# 24Vto12V_v2_1_2025-04-05_21-50-08.net
KiCad netlist of a schematic drawn in EasyEDA Pro
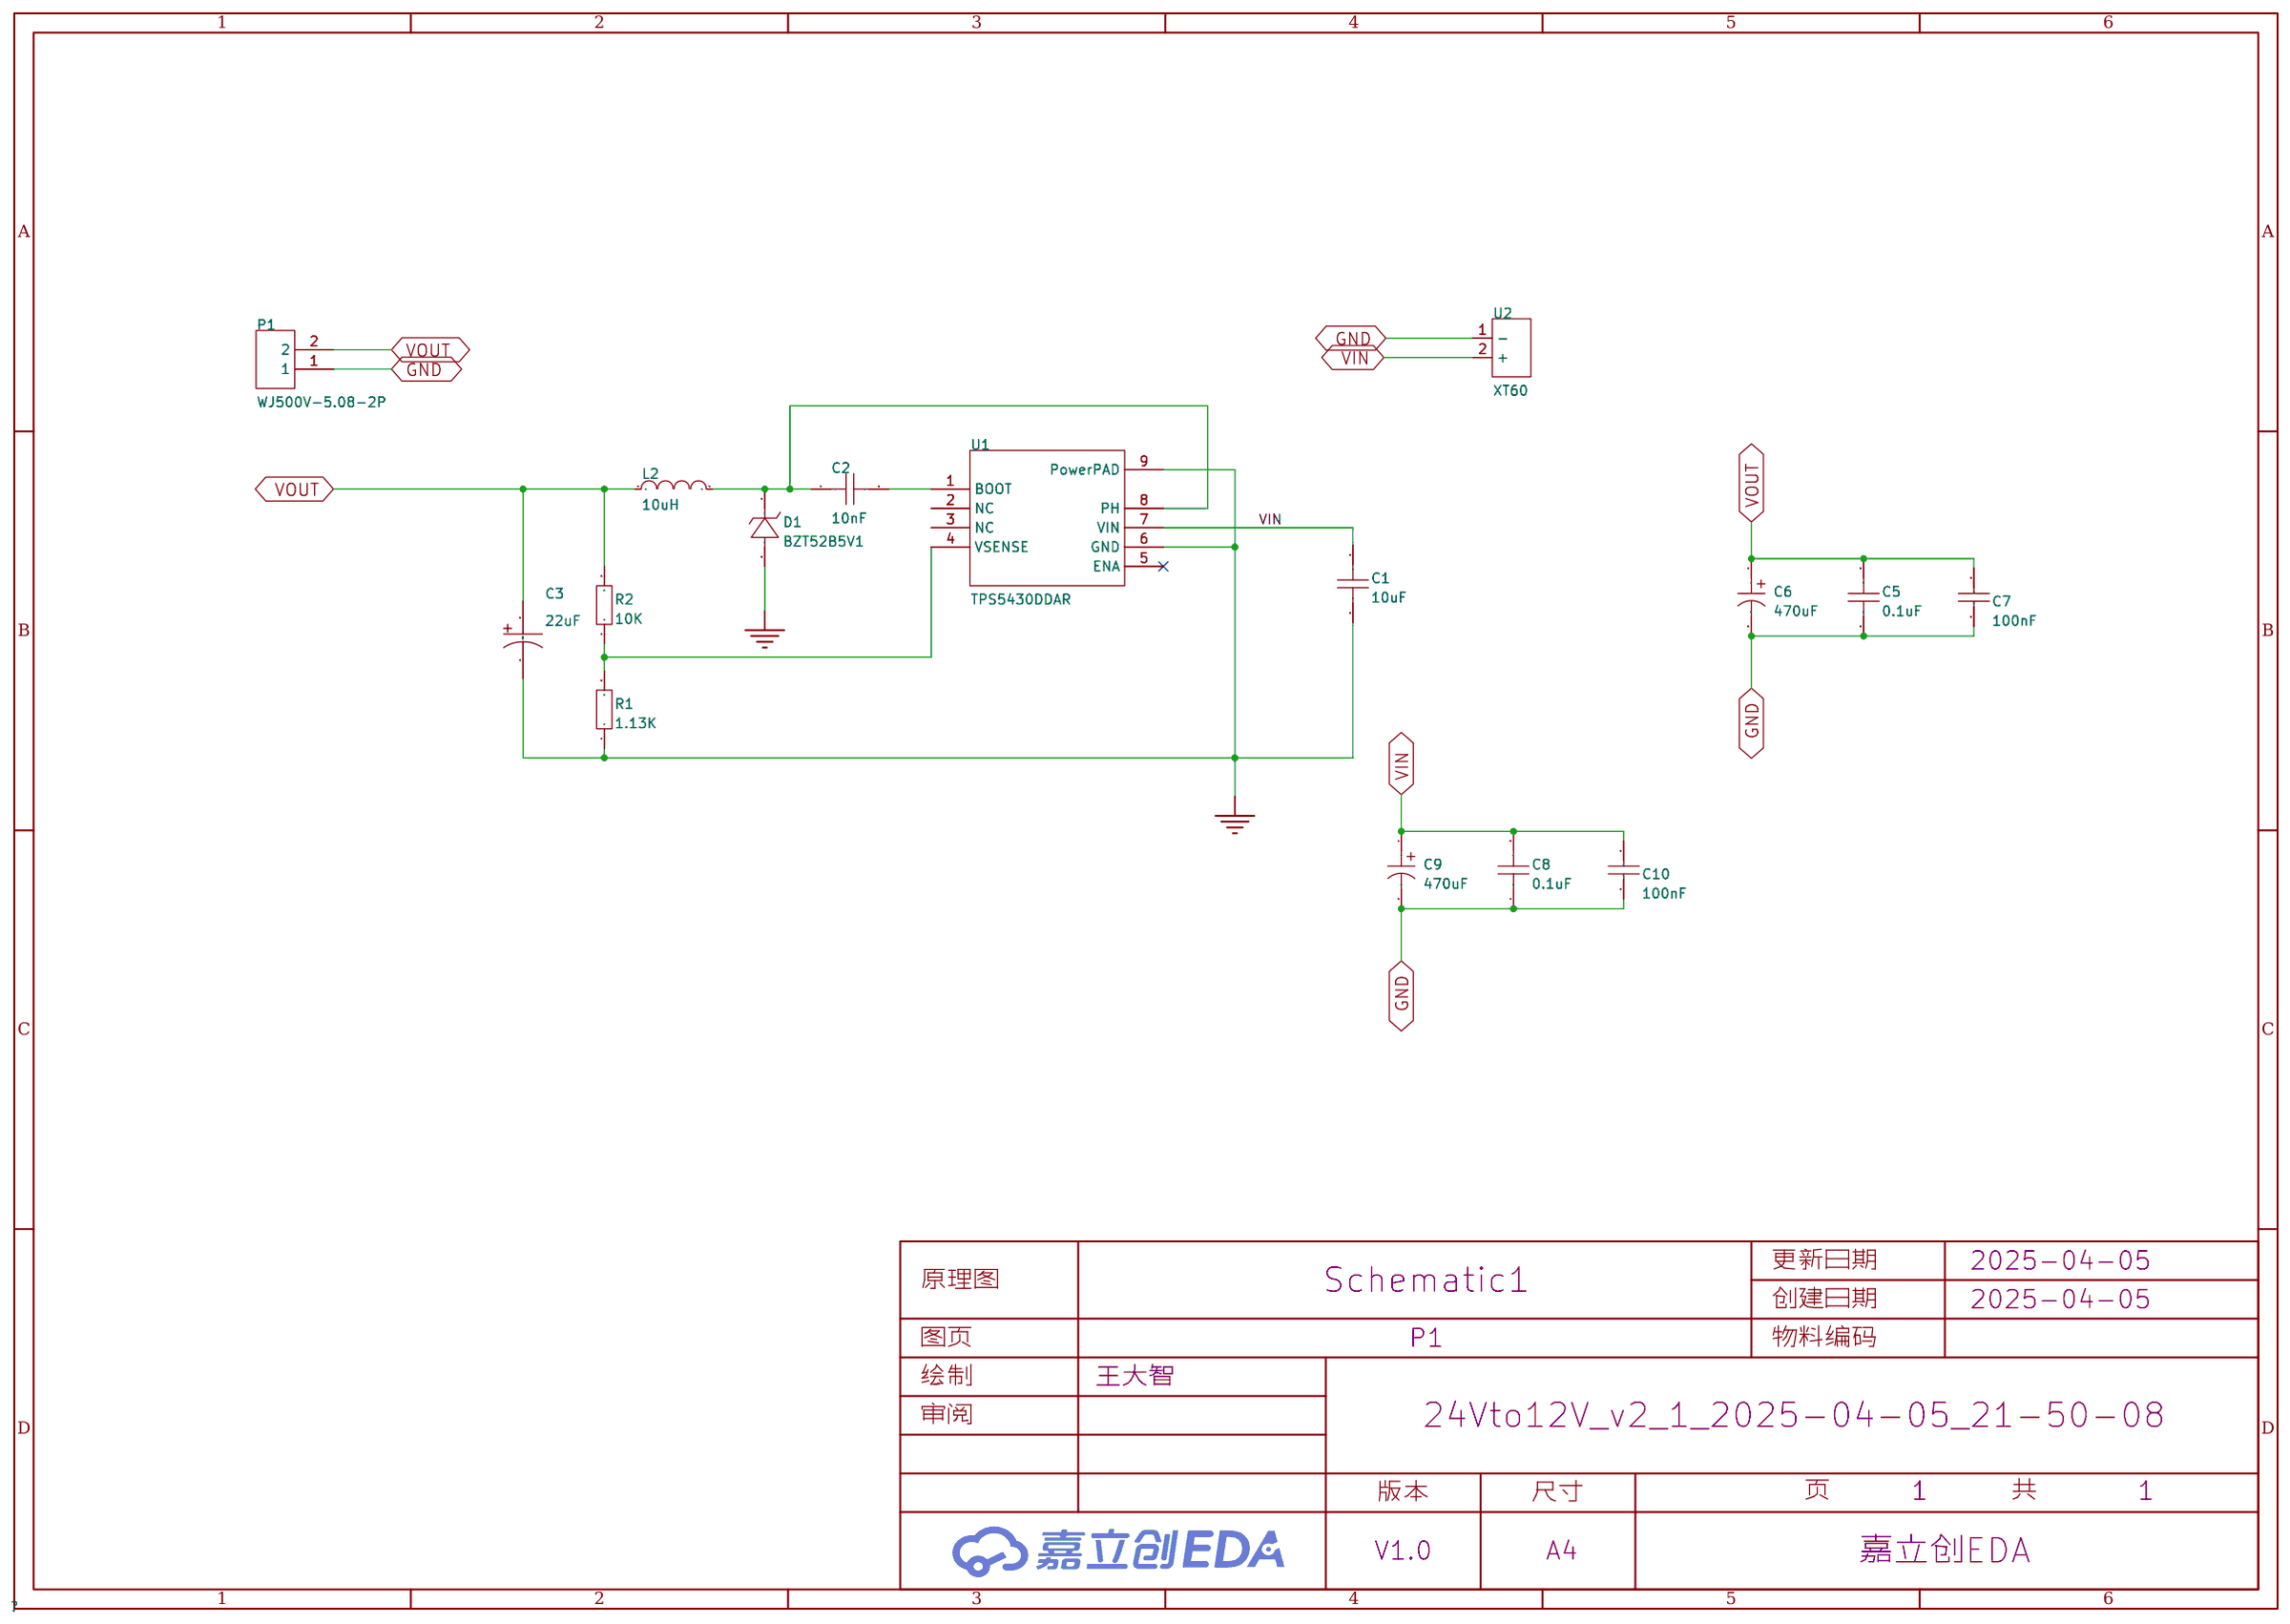
[diagram p0: schematic sheet]

(export (version "E")
  (design (tool "Eeschema 10.0.6"))
  (components
    (comp (ref "C1")
      (value "10uF")
      (footprint "easyedapro:C0603")
      (libsource (lib "easyedapro") (part "CapAcitance"))
    )
    (comp (ref "C2")
      (value "10nF")
      (footprint "easyedapro:C0603")
      (libsource (lib "easyedapro") (part "CapAcitance"))
    )
    (comp (ref "C3")
      (value "22uF")
      (footprint "easyedapro:CAP-SMD_L3.5-W2.8-R-RD")
      (description "容值:22uF;精度:±10%;额定电压:20V;等效串联电阻:400mΩ@100kHz;")
      (fields
        (field (name "Manufacturer Part") "TPSB226K020R0400")
        (field (name "Manufacturer") "Kyocera AVX")
      )
      (libsource (lib "easyedapro") (part "TPSB226K020R0400"))
    )
    (comp (ref "C5")
      (value "0.1uF")
      (footprint "easyedapro:C0603")
      (libsource (lib "easyedapro") (part "CapAcitance"))
    )
    (comp (ref "C6")
      (value "470uF")
      (footprint "easyedapro:CAP-TH_BD8.0-P3.50-D0.6-FD_1")
      (description "容值:470uF;额定电压:25V;")
      (fields
        (field (name "Manufacturer Part") "CD2884771EM0812VFL")
        (field (name "Manufacturer") "HRK(鸿瑞凯电子)")
      )
      (libsource (lib "easyedapro") (part "CD2884771EM0812VFL"))
    )
    (comp (ref "C7")
      (value "100nF")
      (footprint "easyedapro:CAP-TH_L8.5-W5.0-P5.00-D1.2")
      (description "容值:100nF;精度:±20%;额定电压:50V;温度系数:Y5V;")
      (fields (field (name "Manufacturer Part") "CT4-0805Y104M500F3") (field (name "Manufacturer") "FH(风华)"))
      (libsource (lib "easyedapro") (part "CT4-0805Y104M500F3"))
    )
    (comp (ref "C8")
      (value "0.1uF")
      (footprint "easyedapro:C0603")
      (libsource (lib "easyedapro") (part "CapAcitance"))
    )
    (comp (ref "C9")
      (value "470uF")
      (footprint "easyedapro:CAP-TH_BD8.0-P3.50-D0.6-FD_1")
      (description "容值:470uF;额定电压:25V;")
      (fields
        (field (name "Manufacturer Part") "CD2884771EM0812VFL")
        (field (name "Manufacturer") "HRK(鸿瑞凯电子)")
      )
      (libsource (lib "easyedapro") (part "CD2884771EM0812VFL"))
    )
    (comp (ref "C10")
      (value "100nF")
      (footprint "easyedapro:CAP-TH_L8.5-W5.0-P5.00-D1.2")
      (description "容值:100nF;精度:±20%;额定电压:50V;温度系数:Y5V;")
      (fields (field (name "Manufacturer Part") "CT4-0805Y104M500F3") (field (name "Manufacturer") "FH(风华)"))
      (libsource (lib "easyedapro") (part "CT4-0805Y104M500F3"))
    )
    (comp (ref "D1")
      (value "BZT52B5V1")
      (footprint "easyedapro:SOD-123_L2.7-W1.6-LS3.7-RD")
      (description "二极管配置:独立式;稳压值(标称值):5.1V;稳压值(范围):5V~5.2V;耗散功率(Pd):500mW;")
      (fields (field (name "Manufacturer") "宏嘉诚"))
      (libsource (lib "easyedapro") (part "BZT52B5V1_C19077393"))
    )
    (comp (ref "L2")
      (value "10uH")
      (footprint "easyedapro:IND-SMD_L11.5-W10.0_MCF-1050")
      (description "电感值:10uH;精度:±20%;额定电流:5.5A;")
      (fields (field (name "Manufacturer Part") "MS1040-100M") (field (name "Manufacturer") "COILMX(迈翔科技)"))
      (libsource (lib "easyedapro") (part "MS1040-100M"))
    )
    (comp (ref "P1")
      (value "WJ500V-5.08-2P")
      (footprint "easyedapro:CONN-TH_2P-P5.00_WJ500V-5.08-2P")
      (fields (field (name "Manufacturer") "KANGNEX(康奈克斯电气)"))
      (libsource (lib "easyedapro") (part "WJ500V-5.08-2P-14-00A"))
    )
    (comp (ref "R1")
      (value "1.13K")
      (footprint "easyedapro:R0603")
      (libsource (lib "easyedapro") (part "电阻"))
    )
    (comp (ref "R2") (value "10K") (footprint "easyedapro:R0603") (libsource (lib "easyedapro") (part "电阻")))
    (comp (ref "U1")
      (value "TPS5430DDAR")
      (footprint "easyedapro:ESOP-8_L4.9-W3.9-P1.27-LS6.0-TL-EP")
      (description "功能类型:降压型;输出类型:可调;工作电压:5.5V~36V;输出电压:1.221V~32.04V;输出电流:3A;")
      (fields (field (name "Manufacturer") "TI(德州仪器)"))
      (libsource (lib "easyedapro") (part "TPS5430DDAR"))
    )
    (comp (ref "U2")
      (value "XT60")
      (footprint "easyedapro:CONN-TH_XT60")
      (description "类别:-;类型1:-;")
      (fields (field (name "Manufacturer") "AMASS(艾迈斯)"))
      (libsource (lib "easyedapro") (part "XT60"))
    )
  )
  (nets
    (net (code "1") (name "GND") (class "Default")
      (node (ref "C1") (pin "1") (pinfunction "1_1") (pintype "input"))
      (node (ref "C10") (pin "1") (pinfunction "1_1") (pintype "input"))
      (node (ref "C3") (pin "2") (pinfunction "2_2") (pintype "unspecified"))
      (node (ref "C5") (pin "1") (pinfunction "1_1") (pintype "input"))
      (node (ref "C6") (pin "2") (pinfunction "2_2") (pintype "input"))
      (node (ref "C7") (pin "1") (pinfunction "1_1") (pintype "input"))
      (node (ref "C8") (pin "1") (pinfunction "1_1") (pintype "input"))
      (node (ref "C9") (pin "2") (pinfunction "2_2") (pintype "input"))
      (node (ref "D1") (pin "2") (pinfunction "A_2") (pintype "unspecified"))
      (node (ref "P1") (pin "1") (pinfunction "1_1") (pintype "unspecified"))
      (node (ref "R1") (pin "1") (pinfunction "1_1") (pintype "input"))
      (node (ref "U1") (pin "6") (pinfunction "GND_6") (pintype "unspecified"))
      (node (ref "U1") (pin "9") (pinfunction "PowerPAD_9") (pintype "unspecified"))
      (node (ref "U2") (pin "1") (pinfunction "-_1") (pintype "unspecified"))
    )
    (net (code "2") (name "Net-(D1-K)") (class "Default")
      (node (ref "C2") (pin "1") (pinfunction "1_1") (pintype "input"))
      (node (ref "D1") (pin "1") (pinfunction "K_1") (pintype "unspecified"))
      (node (ref "L2") (pin "2") (pinfunction "2_2") (pintype "unspecified"))
      (node (ref "U1") (pin "8") (pinfunction "PH_8") (pintype "unspecified"))
    )
    (net (code "3") (name "Net-(U1-BOOT)") (class "Default")
      (node (ref "C2") (pin "2") (pinfunction "2_2") (pintype "input"))
      (node (ref "U1") (pin "1") (pinfunction "BOOT_1") (pintype "unspecified"))
    )
    (net (code "4") (name "Net-(U1-VSENSE)") (class "Default")
      (node (ref "R1") (pin "2") (pinfunction "2_2") (pintype "input"))
      (node (ref "R2") (pin "1") (pinfunction "1_1") (pintype "input"))
      (node (ref "U1") (pin "4") (pinfunction "VSENSE_4") (pintype "unspecified"))
    )
    (net (code "5") (name "VIN") (class "Default")
      (node (ref "C1") (pin "2") (pinfunction "2_2") (pintype "input"))
      (node (ref "C10") (pin "2") (pinfunction "2_2") (pintype "input"))
      (node (ref "C8") (pin "2") (pinfunction "2_2") (pintype "input"))
      (node (ref "C9") (pin "1") (pinfunction "1_1") (pintype "input"))
      (node (ref "U1") (pin "7") (pinfunction "VIN_7") (pintype "unspecified"))
      (node (ref "U2") (pin "2") (pinfunction "+_2") (pintype "unspecified"))
    )
    (net (code "6") (name "VOUT") (class "Default")
      (node (ref "C3") (pin "1") (pinfunction "1_1") (pintype "unspecified"))
      (node (ref "C5") (pin "2") (pinfunction "2_2") (pintype "input"))
      (node (ref "C6") (pin "1") (pinfunction "1_1") (pintype "input"))
      (node (ref "C7") (pin "2") (pinfunction "2_2") (pintype "input"))
      (node (ref "L2") (pin "1") (pinfunction "1_1") (pintype "unspecified"))
      (node (ref "P1") (pin "2") (pinfunction "2_2") (pintype "unspecified"))
      (node (ref "R2") (pin "2") (pinfunction "2_2") (pintype "input"))
    )
    (net (code "7") (name "unconnected-(U1-ENA-Pad5)") (class "Default")
      (node (ref "U1") (pin "5") (pinfunction "ENA_5") (pintype "unspecified+no_connect"))
    )
    (net (code "8") (name "unconnected-(U1-NC-Pad2)") (class "Default")
      (node (ref "U1") (pin "2") (pinfunction "NC_2") (pintype "unspecified"))
    )
    (net (code "9") (name "unconnected-(U1-NC-Pad3)") (class "Default")
      (node (ref "U1") (pin "3") (pinfunction "NC_3") (pintype "unspecified"))
    )
  )
)
